# Mainboard_Power_Interface.net
KiCad netlist of a schematic drawn in Altium Designer
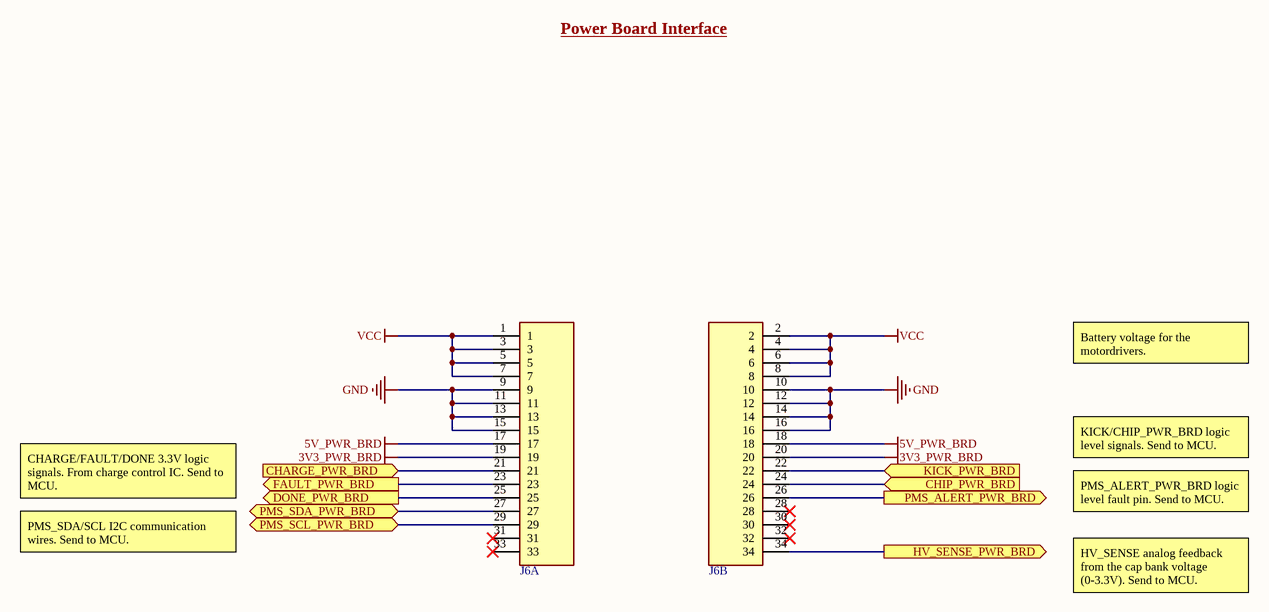
[diagram p0: Mainboard_Power_Interface.SchDoc]

(export (version "E")
  (design (tool "Eeschema 10.0.6"))
  (components
    (comp (ref "J6")
      (value "0.1\" Header Female 34")
      (footprint "SAMTEC-SSM-117-X-DV")
      (description "Female Header THRU 34POS 2ROW 0.1\" (2.54mm) pitch")
      (libsource (lib "") (part "CN HDR 34POS 2x17_1"))
    )
  )
  (nets
    (net (code "1") (name "/CHARGE_PWR_BRD") (class "Default")
      (node (ref "J6") (pin "21") (pinfunction "21_21") (pintype "passive"))
    )
    (net (code "2") (name "/CHIP_PWR_BRD") (class "Default")
      (node (ref "J6") (pin "24") (pinfunction "24_24") (pintype "passive"))
    )
    (net (code "3") (name "/DONE_PWR_BRD") (class "Default")
      (node (ref "J6") (pin "25") (pinfunction "25_25") (pintype "passive"))
    )
    (net (code "4") (name "/FAULT_PWR_BRD") (class "Default")
      (node (ref "J6") (pin "23") (pinfunction "23_23") (pintype "passive"))
    )
    (net (code "5") (name "/HV_SENSE_PWR_BRD") (class "Default")
      (node (ref "J6") (pin "34") (pinfunction "34_34") (pintype "passive"))
    )
    (net (code "6") (name "/KICK_PWR_BRD") (class "Default")
      (node (ref "J6") (pin "22") (pinfunction "22_22") (pintype "passive"))
    )
    (net (code "7") (name "/PMS_ALERT_PWR_BRD") (class "Default")
      (node (ref "J6") (pin "26") (pinfunction "26_26") (pintype "passive"))
    )
    (net (code "8") (name "/PMS_SCL_PWR_BRD") (class "Default")
      (node (ref "J6") (pin "29") (pinfunction "29_29") (pintype "passive"))
    )
    (net (code "9") (name "/PMS_SDA_PWR_BRD") (class "Default")
      (node (ref "J6") (pin "27") (pinfunction "27_27") (pintype "passive"))
    )
    (net (code "10") (name "3V3_PWR_BRD") (class "Default")
      (node (ref "J6") (pin "19") (pinfunction "19_19") (pintype "passive"))
      (node (ref "J6") (pin "20") (pinfunction "20_20") (pintype "passive"))
    )
    (net (code "11") (name "5V_PWR_BRD") (class "Default")
      (node (ref "J6") (pin "17") (pinfunction "17_17") (pintype "passive"))
      (node (ref "J6") (pin "18") (pinfunction "18_18") (pintype "passive"))
    )
    (net (code "12") (name "GND") (class "Default")
      (node (ref "J6") (pin "10") (pinfunction "10_10") (pintype "passive"))
      (node (ref "J6") (pin "11") (pinfunction "11_11") (pintype "passive"))
      (node (ref "J6") (pin "12") (pinfunction "12_12") (pintype "passive"))
      (node (ref "J6") (pin "13") (pinfunction "13_13") (pintype "passive"))
      (node (ref "J6") (pin "14") (pinfunction "14_14") (pintype "passive"))
      (node (ref "J6") (pin "15") (pinfunction "15_15") (pintype "passive"))
      (node (ref "J6") (pin "16") (pinfunction "16_16") (pintype "passive"))
      (node (ref "J6") (pin "9") (pinfunction "9_9") (pintype "passive"))
    )
    (net (code "13") (name "VCC") (class "Default")
      (node (ref "J6") (pin "1") (pinfunction "1_1") (pintype "passive"))
      (node (ref "J6") (pin "2") (pinfunction "2_2") (pintype "passive"))
      (node (ref "J6") (pin "3") (pinfunction "3_3") (pintype "passive"))
      (node (ref "J6") (pin "4") (pinfunction "4_4") (pintype "passive"))
      (node (ref "J6") (pin "5") (pinfunction "5_5") (pintype "passive"))
      (node (ref "J6") (pin "6") (pinfunction "6_6") (pintype "passive"))
      (node (ref "J6") (pin "7") (pinfunction "7_7") (pintype "passive"))
      (node (ref "J6") (pin "8") (pinfunction "8_8") (pintype "passive"))
    )
    (net (code "14") (name "unconnected-(J6-Pad28)") (class "Default")
      (node (ref "J6") (pin "28") (pinfunction "28_28") (pintype "passive+no_connect"))
    )
    (net (code "15") (name "unconnected-(J6-Pad30)") (class "Default")
      (node (ref "J6") (pin "30") (pinfunction "30_30") (pintype "passive+no_connect"))
    )
    (net (code "16") (name "unconnected-(J6-Pad31)") (class "Default")
      (node (ref "J6") (pin "31") (pinfunction "31_31") (pintype "passive+no_connect"))
    )
    (net (code "17") (name "unconnected-(J6-Pad32)") (class "Default")
      (node (ref "J6") (pin "32") (pinfunction "32_32") (pintype "passive+no_connect"))
    )
    (net (code "18") (name "unconnected-(J6-Pad33)") (class "Default")
      (node (ref "J6") (pin "33") (pinfunction "33_33") (pintype "passive+no_connect"))
    )
  )
)
